# CNC1000.net
KiCad netlist of a schematic drawn in EAGLE
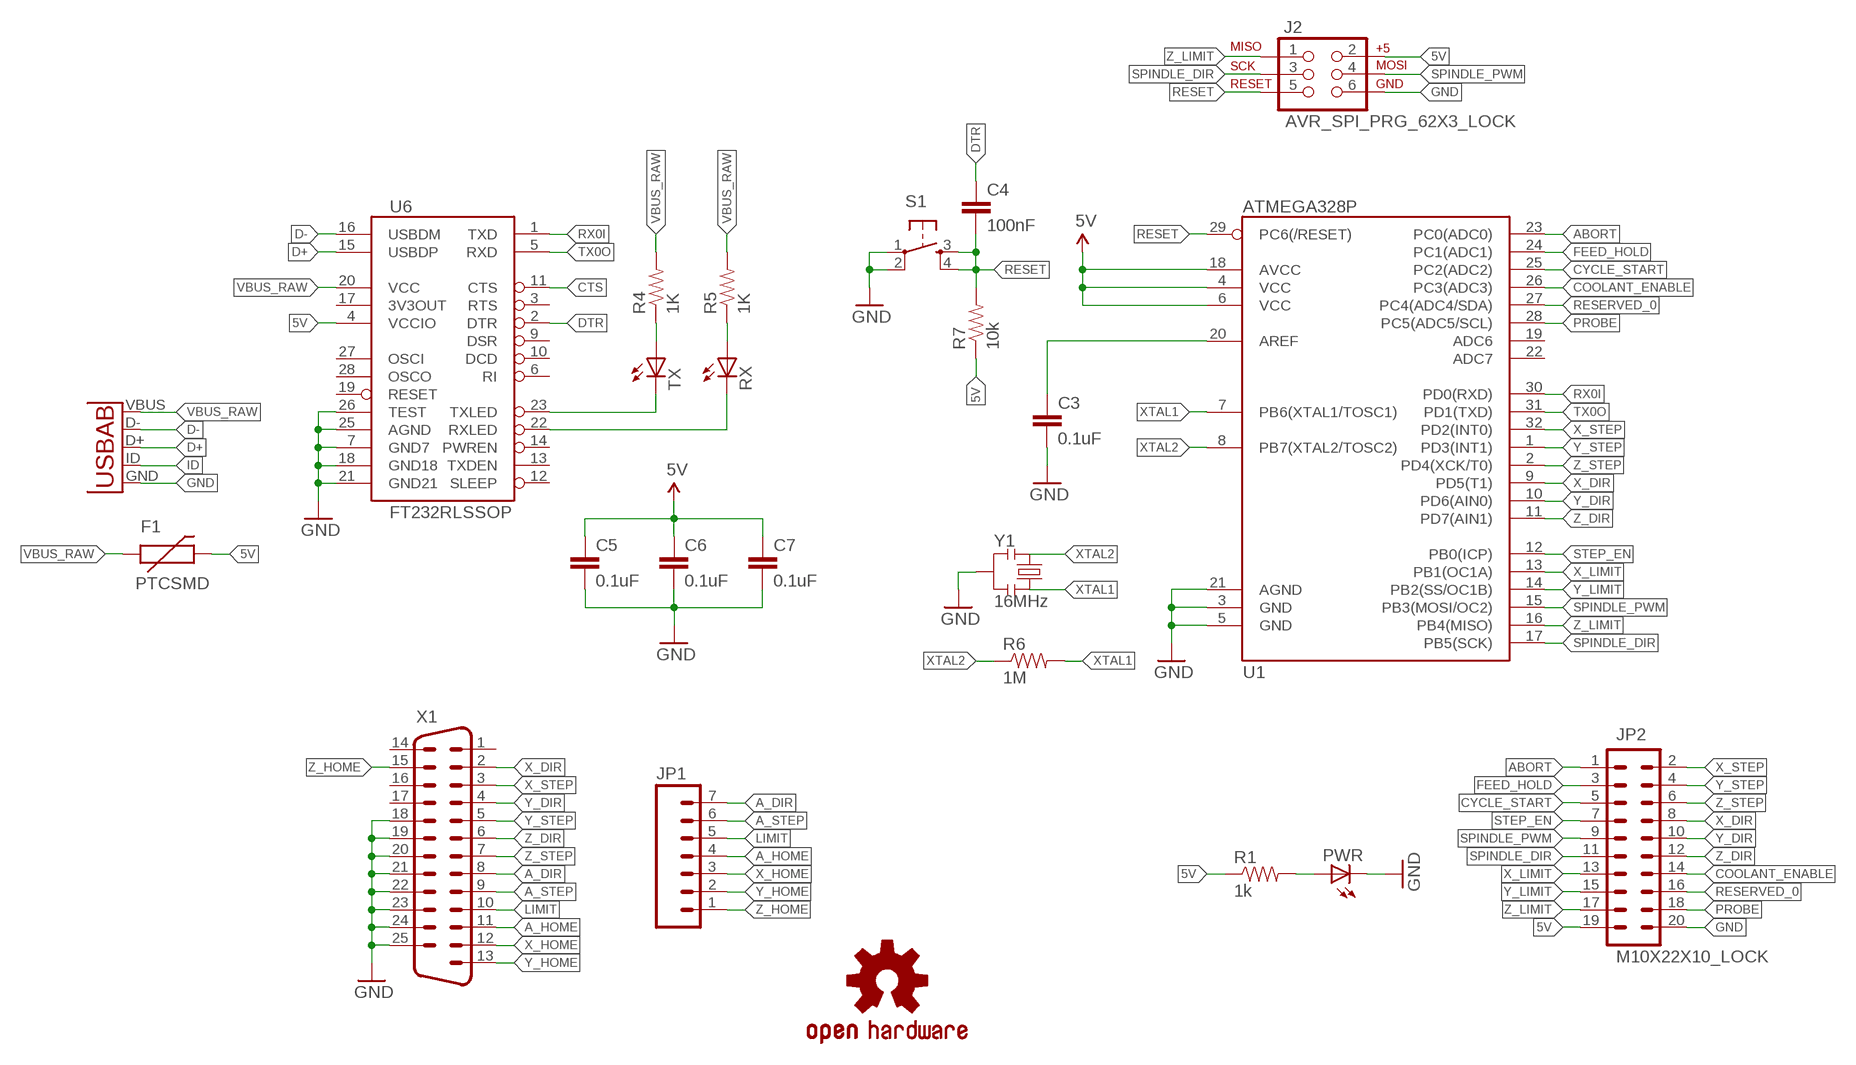
[diagram p0: schematic, sheet 1]

(export (version "E")
  (design (tool "Eeschema 10.0.6"))
  (components
    (comp (ref "C3")
      (value "0.1uF")
      (footprint "eagle-import:0805")
      (libsource (lib "eagle-import") (part "CAP0805"))
    )
    (comp (ref "C4")
      (value "100nF")
      (footprint "eagle-import:0805")
      (libsource (lib "eagle-import") (part "CAP0805"))
    )
    (comp (ref "C5")
      (value "0.1uF")
      (footprint "eagle-import:0805")
      (libsource (lib "eagle-import") (part "evanli_CAP0805"))
    )
    (comp (ref "C6")
      (value "0.1uF")
      (footprint "eagle-import:0805")
      (libsource (lib "eagle-import") (part "evanli_CAP0805"))
    )
    (comp (ref "C7")
      (value "0.1uF")
      (footprint "eagle-import:0805")
      (libsource (lib "eagle-import") (part "evanli_CAP0805"))
    )
    (comp (ref "F1")
      (value "PTCSMD")
      (footprint "eagle-import:PTC-1206")
      (libsource (lib "eagle-import") (part "PTCSMD"))
    )
    (comp (ref "J2")
      (value "AVR_SPI_PRG_62X3_LOCK")
      (footprint "eagle-import:2X3_LOCK")
      (libsource (lib "eagle-import") (part "AVR_SPI_PRG_62X3_LOCK"))
    )
    (comp (ref "JP1")
      (value "M07LOCK")
      (footprint "eagle-import:1X07_LOCK")
      (libsource (lib "eagle-import") (part "M07LOCK"))
    )
    (comp (ref "JP2")
      (value "M10X22X10_LOCK")
      (footprint "eagle-import:2X10_LOCK")
      (libsource (lib "eagle-import") (part "M10X22X10_LOCK"))
    )
    (comp (ref "LOGO2")
      (value "OSHW-LOGOM")
      (footprint "eagle-import:OSHW-LOGO-M")
      (libsource (lib "eagle-import") (part "OSHW-LOGOM"))
    )
    (comp (ref "PWR")
      (value "LED0603")
      (footprint "eagle-import:LED-0603")
      (libsource (lib "eagle-import") (part "LED0603"))
    )
    (comp (ref "R1")
      (value "1k")
      (footprint "eagle-import:0805")
      (libsource (lib "eagle-import") (part "RESISTOR0805-RES"))
    )
    (comp (ref "R4")
      (value "1K")
      (footprint "eagle-import:0805")
      (libsource (lib "eagle-import") (part "RESISTOR0805-RES"))
    )
    (comp (ref "R5")
      (value "1K")
      (footprint "eagle-import:0805")
      (libsource (lib "eagle-import") (part "RESISTOR0805-RES"))
    )
    (comp (ref "R6")
      (value "1M")
      (footprint "eagle-import:0805")
      (libsource (lib "eagle-import") (part "RESISTOR0805-RES"))
    )
    (comp (ref "R7")
      (value "10k")
      (footprint "eagle-import:0805")
      (libsource (lib "eagle-import") (part "RESISTOR0805-RES"))
    )
    (comp (ref "RX")
      (value "LED0603")
      (footprint "eagle-import:LED-0603")
      (libsource (lib "eagle-import") (part "LED0603"))
    )
    (comp (ref "S1")
      (value "TAC_SWITCHSMD")
      (footprint "eagle-import:TACTILE_SWITCH_SMD")
      (libsource (lib "eagle-import") (part "TAC_SWITCHSMD"))
    )
    (comp (ref "TX")
      (value "LED0603")
      (footprint "eagle-import:LED-0603")
      (libsource (lib "eagle-import") (part "LED0603"))
    )
    (comp (ref "U1")
      (value "ATMEGA328P")
      (footprint "eagle-import:TQFP32-08")
      (libsource (lib "eagle-import") (part "ATMEGA328_SMT"))
    )
    (comp (ref "U4")
      (value "USB-AB\"")
      (footprint "eagle-import:USB_AB_MICRO_1_1_V2")
      (libsource (lib "eagle-import") (part "USB-AB{dblquote}"))
    )
    (comp (ref "U6")
      (value "FT232RLSSOP")
      (footprint "eagle-import:SSOP28DB")
      (libsource (lib "eagle-import") (part "FT232RLSSOP"))
    )
    (comp (ref "X1")
      (value "DB25TE")
      (footprint "eagle-import:TE1734350")
      (libsource (lib "eagle-import") (part "DB25TE"))
    )
    (comp (ref "Y1")
      (value "16MHz")
      (footprint "eagle-import:PRQC16.00SR1010V00L")
      (libsource (lib "eagle-import") (part "PRQC16.00SR1010V00LSMD"))
    )
  )
  (nets
    (net (code "1") (name "5V") (class "Default")
      (node (ref "C5") (pin "1") (pinfunction "1_1") (pintype "passive"))
      (node (ref "C6") (pin "1") (pinfunction "1_1") (pintype "passive"))
      (node (ref "C7") (pin "1") (pinfunction "1_1") (pintype "passive"))
      (node (ref "F1") (pin "2") (pinfunction "2_2") (pintype "bidirectional"))
      (node (ref "J2") (pin "2") (pinfunction "2_2") (pintype "passive"))
      (node (ref "JP2") (pin "19") (pinfunction "19_19") (pintype "passive"))
      (node (ref "R1") (pin "1") (pinfunction "1_1") (pintype "passive"))
      (node (ref "R7") (pin "1") (pinfunction "1_1") (pintype "passive"))
      (node (ref "U1") (pin "18") (pinfunction "AVCC_18") (pintype "bidirectional"))
      (node (ref "U1") (pin "4") (pinfunction "VCC_4") (pintype "bidirectional"))
      (node (ref "U1") (pin "6") (pinfunction "VCC_6") (pintype "bidirectional"))
      (node (ref "U6") (pin "4") (pinfunction "VCCIO_4") (pintype "power_in"))
    )
    (net (code "2") (name "ABORT") (class "Default")
      (node (ref "JP2") (pin "1") (pinfunction "1_1") (pintype "passive"))
      (node (ref "U1") (pin "23") (pinfunction "PC0(ADC0)_23") (pintype "bidirectional"))
    )
    (net (code "3") (name "A_DIR") (class "Default")
      (node (ref "JP1") (pin "7") (pinfunction "7_7") (pintype "passive"))
      (node (ref "X1") (pin "8") (pinfunction "8_8") (pintype "passive"))
    )
    (net (code "4") (name "A_HOME") (class "Default")
      (node (ref "JP1") (pin "4") (pinfunction "4_4") (pintype "passive"))
      (node (ref "X1") (pin "11") (pinfunction "11_11") (pintype "passive"))
    )
    (net (code "5") (name "A_STEP") (class "Default")
      (node (ref "JP1") (pin "6") (pinfunction "6_6") (pintype "passive"))
      (node (ref "X1") (pin "9") (pinfunction "9_9") (pintype "passive"))
    )
    (net (code "6") (name "COOLANT_ENABLE") (class "Default")
      (node (ref "JP2") (pin "14") (pinfunction "14_14") (pintype "passive"))
      (node (ref "U1") (pin "26") (pinfunction "PC3(ADC3)_26") (pintype "bidirectional"))
    )
    (net (code "7") (name "CTS") (class "Default")
      (node (ref "U6") (pin "11") (pinfunction "CTS_11") (pintype "input"))
    )
    (net (code "8") (name "CYCLE_START") (class "Default")
      (node (ref "JP2") (pin "5") (pinfunction "5_5") (pintype "passive"))
      (node (ref "U1") (pin "25") (pinfunction "PC2(ADC2)_25") (pintype "bidirectional"))
    )
    (net (code "9") (name "D+") (class "Default")
      (node (ref "U4") (pin "D+") (pinfunction "D+_D+") (pintype "bidirectional"))
      (node (ref "U6") (pin "15") (pinfunction "USBDP_15") (pintype "bidirectional"))
    )
    (net (code "10") (name "D-") (class "Default")
      (node (ref "U4") (pin "D-") (pinfunction "D-_D-") (pintype "bidirectional"))
      (node (ref "U6") (pin "16") (pinfunction "USBDM_16") (pintype "bidirectional"))
    )
    (net (code "11") (name "DTR") (class "Default")
      (node (ref "C4") (pin "1") (pinfunction "1_1") (pintype "passive"))
      (node (ref "U6") (pin "2") (pinfunction "DTR_2") (pintype "output"))
    )
    (net (code "12") (name "FEED_HOLD") (class "Default")
      (node (ref "JP2") (pin "3") (pinfunction "3_3") (pintype "passive"))
      (node (ref "U1") (pin "24") (pinfunction "PC1(ADC1)_24") (pintype "bidirectional"))
    )
    (net (code "13") (name "GND") (class "Default")
      (node (ref "C3") (pin "2") (pinfunction "2_2") (pintype "passive"))
      (node (ref "C5") (pin "2") (pinfunction "2_2") (pintype "passive"))
      (node (ref "C6") (pin "2") (pinfunction "2_2") (pintype "passive"))
      (node (ref "C7") (pin "2") (pinfunction "2_2") (pintype "passive"))
      (node (ref "J2") (pin "6") (pinfunction "6_6") (pintype "passive"))
      (node (ref "JP2") (pin "20") (pinfunction "20_20") (pintype "passive"))
      (node (ref "PWR") (pin "C") (pinfunction "C_C") (pintype "passive"))
      (node (ref "S1") (pin "1") (pinfunction "1_1") (pintype "passive"))
      (node (ref "S1") (pin "2") (pinfunction "2_2") (pintype "passive"))
      (node (ref "U1") (pin "21") (pinfunction "AGND_21") (pintype "bidirectional"))
      (node (ref "U1") (pin "3") (pinfunction "GND_3") (pintype "bidirectional"))
      (node (ref "U1") (pin "5") (pinfunction "GND_5") (pintype "bidirectional"))
      (node (ref "U4") (pin "GND") (pinfunction "GND_GND") (pintype "bidirectional"))
      (node (ref "U6") (pin "18") (pinfunction "GND18_18") (pintype "power_in"))
      (node (ref "U6") (pin "21") (pinfunction "GND21_21") (pintype "power_in"))
      (node (ref "U6") (pin "25") (pinfunction "AGND_25") (pintype "power_in"))
      (node (ref "U6") (pin "26") (pinfunction "TEST_26") (pintype "input"))
      (node (ref "U6") (pin "7") (pinfunction "GND7_7") (pintype "power_in"))
      (node (ref "X1") (pin "18") (pinfunction "18_18") (pintype "passive"))
      (node (ref "X1") (pin "19") (pinfunction "19_19") (pintype "passive"))
      (node (ref "X1") (pin "20") (pinfunction "20_20") (pintype "passive"))
      (node (ref "X1") (pin "21") (pinfunction "21_21") (pintype "passive"))
      (node (ref "X1") (pin "22") (pinfunction "22_22") (pintype "passive"))
      (node (ref "X1") (pin "23") (pinfunction "23_23") (pintype "passive"))
      (node (ref "X1") (pin "24") (pinfunction "24_24") (pintype "passive"))
      (node (ref "X1") (pin "25") (pinfunction "25_25") (pintype "passive"))
      (node (ref "Y1") (pin "P$2") (pinfunction "2_P$2") (pintype "passive"))
    )
    (net (code "14") (name "ID") (class "Default")
      (node (ref "U4") (pin "ID") (pinfunction "USBID_ID") (pintype "bidirectional"))
    )
    (net (code "15") (name "LIMIT") (class "Default")
      (node (ref "JP1") (pin "5") (pinfunction "5_5") (pintype "passive"))
      (node (ref "X1") (pin "10") (pinfunction "10_10") (pintype "passive"))
    )
    (net (code "16") (name "Net-(PWR-PadA)") (class "Default")
      (node (ref "PWR") (pin "A") (pinfunction "A_A") (pintype "passive"))
      (node (ref "R1") (pin "2") (pinfunction "2_2") (pintype "passive"))
    )
    (net (code "17") (name "Net-(R4-Pad1)") (class "Default")
      (node (ref "R4") (pin "1") (pinfunction "1_1") (pintype "passive"))
      (node (ref "TX") (pin "A") (pinfunction "A_A") (pintype "passive"))
    )
    (net (code "18") (name "Net-(R5-Pad1)") (class "Default")
      (node (ref "R5") (pin "1") (pinfunction "1_1") (pintype "passive"))
      (node (ref "RX") (pin "A") (pinfunction "A_A") (pintype "passive"))
    )
    (net (code "19") (name "Net-(U1-AREF)") (class "Default")
      (node (ref "C3") (pin "1") (pinfunction "1_1") (pintype "passive"))
      (node (ref "U1") (pin "20") (pinfunction "AREF_20") (pintype "bidirectional"))
    )
    (net (code "20") (name "Net-(U6-RXLED)") (class "Default")
      (node (ref "RX") (pin "C") (pinfunction "C_C") (pintype "passive"))
      (node (ref "U6") (pin "22") (pinfunction "RXLED_22") (pintype "input"))
    )
    (net (code "21") (name "Net-(U6-TXLED)") (class "Default")
      (node (ref "TX") (pin "C") (pinfunction "C_C") (pintype "passive"))
      (node (ref "U6") (pin "23") (pinfunction "TXLED_23") (pintype "input"))
    )
    (net (code "22") (name "PROBE") (class "Default")
      (node (ref "JP2") (pin "18") (pinfunction "18_18") (pintype "passive"))
      (node (ref "U1") (pin "28") (pinfunction "PC5(ADC5/SCL)_28") (pintype "bidirectional"))
    )
    (net (code "23") (name "RESERVED_0") (class "Default")
      (node (ref "JP2") (pin "16") (pinfunction "16_16") (pintype "passive"))
      (node (ref "U1") (pin "27") (pinfunction "PC4(ADC4/SDA)_27") (pintype "bidirectional"))
    )
    (net (code "24") (name "RESET") (class "Default")
      (node (ref "C4") (pin "2") (pinfunction "2_2") (pintype "passive"))
      (node (ref "J2") (pin "5") (pinfunction "5_5") (pintype "passive"))
      (node (ref "R7") (pin "2") (pinfunction "2_2") (pintype "passive"))
      (node (ref "S1") (pin "3") (pinfunction "3_3") (pintype "passive"))
      (node (ref "S1") (pin "4") (pinfunction "4_4") (pintype "passive"))
      (node (ref "U1") (pin "29") (pinfunction "PC6(/RESET)_29") (pintype "bidirectional"))
    )
    (net (code "25") (name "RX0I") (class "Default")
      (node (ref "U1") (pin "30") (pinfunction "PD0(RXD)_30") (pintype "bidirectional"))
      (node (ref "U6") (pin "1") (pinfunction "TXD_1") (pintype "output"))
    )
    (net (code "26") (name "SPINDLE_DIR") (class "Default")
      (node (ref "J2") (pin "3") (pinfunction "3_3") (pintype "passive"))
      (node (ref "JP2") (pin "11") (pinfunction "11_11") (pintype "passive"))
      (node (ref "U1") (pin "17") (pinfunction "PB5(SCK)_17") (pintype "bidirectional"))
    )
    (net (code "27") (name "SPINDLE_PWM") (class "Default")
      (node (ref "J2") (pin "4") (pinfunction "4_4") (pintype "passive"))
      (node (ref "JP2") (pin "9") (pinfunction "9_9") (pintype "passive"))
      (node (ref "U1") (pin "15") (pinfunction "PB3(MOSI/OC2)_15") (pintype "bidirectional"))
    )
    (net (code "28") (name "STEP_EN") (class "Default")
      (node (ref "JP2") (pin "7") (pinfunction "7_7") (pintype "passive"))
      (node (ref "U1") (pin "12") (pinfunction "PB0(ICP)_12") (pintype "bidirectional"))
    )
    (net (code "29") (name "TX0O") (class "Default")
      (node (ref "U1") (pin "31") (pinfunction "PD1(TXD)_31") (pintype "bidirectional"))
      (node (ref "U6") (pin "5") (pinfunction "RXD_5") (pintype "input"))
    )
    (net (code "30") (name "VBUS_RAW") (class "Default")
      (node (ref "F1") (pin "1") (pinfunction "1_1") (pintype "bidirectional"))
      (node (ref "R4") (pin "2") (pinfunction "2_2") (pintype "passive"))
      (node (ref "R5") (pin "2") (pinfunction "2_2") (pintype "passive"))
      (node (ref "U4") (pin "VBUS") (pinfunction "VBUS_VBUS") (pintype "bidirectional"))
      (node (ref "U6") (pin "20") (pinfunction "VCC_20") (pintype "power_in"))
    )
    (net (code "31") (name "XTAL1") (class "Default")
      (node (ref "R6") (pin "2") (pinfunction "2_2") (pintype "passive"))
      (node (ref "U1") (pin "7") (pinfunction "PB6(XTAL1/TOSC1)_7") (pintype "bidirectional"))
      (node (ref "Y1") (pin "P$3") (pinfunction "3_P$3") (pintype "passive"))
    )
    (net (code "32") (name "XTAL2") (class "Default")
      (node (ref "R6") (pin "1") (pinfunction "1_1") (pintype "passive"))
      (node (ref "U1") (pin "8") (pinfunction "PB7(XTAL2/TOSC2)_8") (pintype "bidirectional"))
      (node (ref "Y1") (pin "P$1") (pinfunction "1_P$1") (pintype "passive"))
    )
    (net (code "33") (name "X_DIR") (class "Default")
      (node (ref "JP2") (pin "8") (pinfunction "8_8") (pintype "passive"))
      (node (ref "U1") (pin "9") (pinfunction "PD5(T1)_9") (pintype "bidirectional"))
      (node (ref "X1") (pin "2") (pinfunction "2_2") (pintype "passive"))
    )
    (net (code "34") (name "X_HOME") (class "Default")
      (node (ref "JP1") (pin "3") (pinfunction "3_3") (pintype "passive"))
      (node (ref "X1") (pin "12") (pinfunction "12_12") (pintype "passive"))
    )
    (net (code "35") (name "X_LIMIT") (class "Default")
      (node (ref "JP2") (pin "13") (pinfunction "13_13") (pintype "passive"))
      (node (ref "U1") (pin "13") (pinfunction "PB1(OC1A)_13") (pintype "bidirectional"))
    )
    (net (code "36") (name "X_STEP") (class "Default")
      (node (ref "JP2") (pin "2") (pinfunction "2_2") (pintype "passive"))
      (node (ref "U1") (pin "32") (pinfunction "PD2(INT0)_32") (pintype "bidirectional"))
      (node (ref "X1") (pin "3") (pinfunction "3_3") (pintype "passive"))
    )
    (net (code "37") (name "Y_DIR") (class "Default")
      (node (ref "JP2") (pin "10") (pinfunction "10_10") (pintype "passive"))
      (node (ref "U1") (pin "10") (pinfunction "PD6(AIN0)_10") (pintype "bidirectional"))
      (node (ref "X1") (pin "4") (pinfunction "4_4") (pintype "passive"))
    )
    (net (code "38") (name "Y_HOME") (class "Default")
      (node (ref "JP1") (pin "2") (pinfunction "2_2") (pintype "passive"))
      (node (ref "X1") (pin "13") (pinfunction "13_13") (pintype "passive"))
    )
    (net (code "39") (name "Y_LIMIT") (class "Default")
      (node (ref "JP2") (pin "15") (pinfunction "15_15") (pintype "passive"))
      (node (ref "U1") (pin "14") (pinfunction "PB2(SS/OC1B)_14") (pintype "bidirectional"))
    )
    (net (code "40") (name "Y_STEP") (class "Default")
      (node (ref "JP2") (pin "4") (pinfunction "4_4") (pintype "passive"))
      (node (ref "U1") (pin "1") (pinfunction "PD3(INT1)_1") (pintype "bidirectional"))
      (node (ref "X1") (pin "5") (pinfunction "5_5") (pintype "passive"))
    )
    (net (code "41") (name "Z_DIR") (class "Default")
      (node (ref "JP2") (pin "12") (pinfunction "12_12") (pintype "passive"))
      (node (ref "U1") (pin "11") (pinfunction "PD7(AIN1)_11") (pintype "bidirectional"))
      (node (ref "X1") (pin "6") (pinfunction "6_6") (pintype "passive"))
    )
    (net (code "42") (name "Z_HOME") (class "Default")
      (node (ref "JP1") (pin "1") (pinfunction "1_1") (pintype "passive"))
      (node (ref "X1") (pin "15") (pinfunction "15_15") (pintype "passive"))
    )
    (net (code "43") (name "Z_LIMIT") (class "Default")
      (node (ref "J2") (pin "1") (pinfunction "1_1") (pintype "passive"))
      (node (ref "JP2") (pin "17") (pinfunction "17_17") (pintype "passive"))
      (node (ref "U1") (pin "16") (pinfunction "PB4(MISO)_16") (pintype "bidirectional"))
    )
    (net (code "44") (name "Z_STEP") (class "Default")
      (node (ref "JP2") (pin "6") (pinfunction "6_6") (pintype "passive"))
      (node (ref "U1") (pin "2") (pinfunction "PD4(XCK/T0)_2") (pintype "bidirectional"))
      (node (ref "X1") (pin "7") (pinfunction "7_7") (pintype "passive"))
    )
    (net (code "45") (name "unconnected-(U1-ADC6-Pad19)") (class "Default")
      (node (ref "U1") (pin "19") (pinfunction "ADC6_19") (pintype "bidirectional"))
    )
    (net (code "46") (name "unconnected-(U1-ADC7-Pad22)") (class "Default")
      (node (ref "U1") (pin "22") (pinfunction "ADC7_22") (pintype "bidirectional"))
    )
    (net (code "47") (name "unconnected-(U6-3V3OUT-Pad17)") (class "Default")
      (node (ref "U6") (pin "17") (pinfunction "3V3OUT_17") (pintype "output"))
    )
    (net (code "48") (name "unconnected-(U6-DCD-Pad10)") (class "Default")
      (node (ref "U6") (pin "10") (pinfunction "DCD_10") (pintype "input"))
    )
    (net (code "49") (name "unconnected-(U6-DSR-Pad9)") (class "Default")
      (node (ref "U6") (pin "9") (pinfunction "DSR_9") (pintype "input"))
    )
    (net (code "50") (name "unconnected-(U6-OSCI-Pad27)") (class "Default")
      (node (ref "U6") (pin "27") (pinfunction "OSCI_27") (pintype "input"))
    )
    (net (code "51") (name "unconnected-(U6-OSCO-Pad28)") (class "Default")
      (node (ref "U6") (pin "28") (pinfunction "OSCO_28") (pintype "output"))
    )
    (net (code "52") (name "unconnected-(U6-PWREN-Pad14)") (class "Default")
      (node (ref "U6") (pin "14") (pinfunction "PWREN_14") (pintype "input"))
    )
    (net (code "53") (name "unconnected-(U6-RESET-Pad19)") (class "Default")
      (node (ref "U6") (pin "19") (pinfunction "RESET_19") (pintype "input"))
    )
    (net (code "54") (name "unconnected-(U6-RI-Pad6)") (class "Default")
      (node (ref "U6") (pin "6") (pinfunction "RI_6") (pintype "input"))
    )
    (net (code "55") (name "unconnected-(U6-RTS-Pad3)") (class "Default")
      (node (ref "U6") (pin "3") (pinfunction "RTS_3") (pintype "output"))
    )
    (net (code "56") (name "unconnected-(U6-SLEEP-Pad12)") (class "Default")
      (node (ref "U6") (pin "12") (pinfunction "SLEEP_12") (pintype "input"))
    )
    (net (code "57") (name "unconnected-(U6-TXDEN-Pad13)") (class "Default")
      (node (ref "U6") (pin "13") (pinfunction "TXDEN_13") (pintype "input"))
    )
    (net (code "58") (name "unconnected-(X1-Pad1)") (class "Default")
      (node (ref "X1") (pin "1") (pinfunction "1_1") (pintype "passive"))
    )
    (net (code "59") (name "unconnected-(X1-Pad14)") (class "Default")
      (node (ref "X1") (pin "14") (pinfunction "14_14") (pintype "passive"))
    )
    (net (code "60") (name "unconnected-(X1-Pad16)") (class "Default")
      (node (ref "X1") (pin "16") (pinfunction "16_16") (pintype "passive"))
    )
    (net (code "61") (name "unconnected-(X1-Pad17)") (class "Default")
      (node (ref "X1") (pin "17") (pinfunction "17_17") (pintype "passive"))
    )
  )
)
